# Nav_MCU_IO.net
KiCad netlist of a schematic drawn in Altium Designer
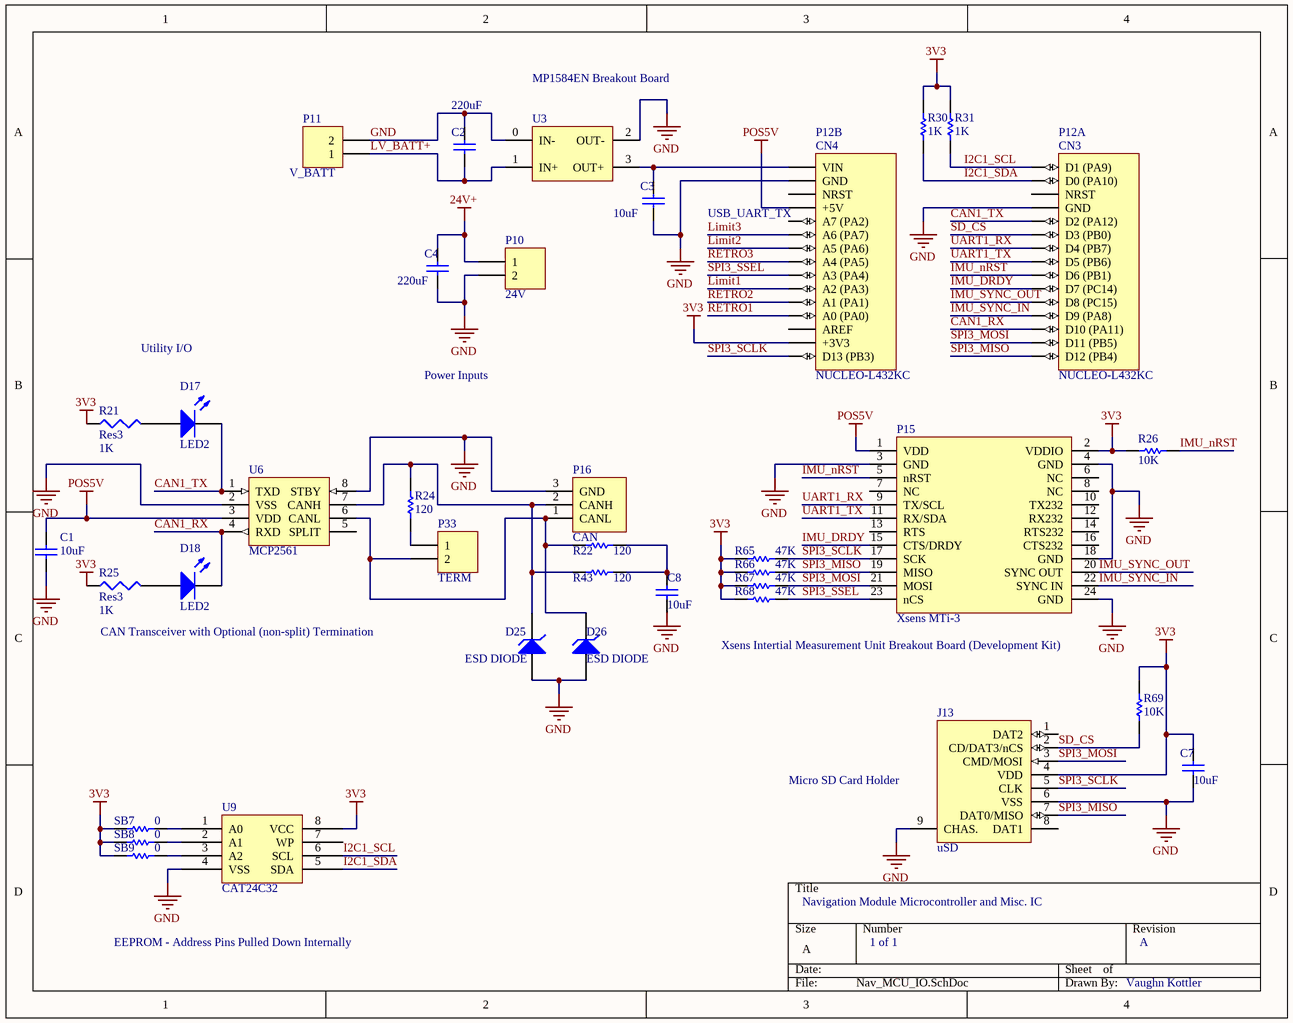
[diagram p0: Nav_MCU_IO.SchDoc]

(export (version "E")
  (design (tool "Eeschema 10.0.6"))
  (components
    (comp (ref "C1")
      (value "10uF")
      (footprint "C1206")
      (description "Capacitor")
      (fields (field (name "Comment") "Cap") (field (name "PUBLISHER") "Altium Limited"))
      (libsource (lib "Miscellaneous Devices") (part "Cap"))
    )
    (comp (ref "C2")
      (value "220uF")
      (footprint "CAPR5-4X5")
      (description "Capacitor")
      (fields (field (name "Comment") "Cap") (field (name "PUBLISHER") "Altium Limited"))
      (libsource (lib "Miscellaneous Devices") (part "Cap"))
    )
    (comp (ref "C3")
      (value "10uF")
      (footprint "C1206")
      (description "Capacitor")
      (fields (field (name "Comment") "Cap") (field (name "PUBLISHER") "Altium Limited"))
      (libsource (lib "Miscellaneous Devices") (part "Cap"))
    )
    (comp (ref "C4")
      (value "220uF")
      (footprint "CAPR5-4X5")
      (description "Capacitor")
      (fields (field (name "Comment") "Cap") (field (name "PUBLISHER") "Altium Limited"))
      (libsource (lib "Miscellaneous Devices") (part "Cap"))
    )
    (comp (ref "C7")
      (value "10uF")
      (footprint "C1206")
      (description "Capacitor")
      (fields (field (name "Comment") "Cap") (field (name "PUBLISHER") "Altium Limited"))
      (libsource (lib "Miscellaneous Devices") (part "Cap"))
    )
    (comp (ref "C8")
      (value "10uF")
      (footprint "C1206")
      (description "Capacitor")
      (fields (field (name "Comment") "Cap") (field (name "PUBLISHER") "Altium Limited"))
      (libsource (lib "Miscellaneous Devices") (part "Cap"))
    )
    (comp (ref "D17")
      (value "LED2")
      (footprint "3.2X1.6X1.1")
      (description "Typical RED, GREEN, YELLOW, AMBER GaAs LED")
      (fields (field (name "PUBLISHER") "Altium Limited"))
      (libsource (lib "Miscellaneous Devices") (part "LED2"))
    )
    (comp (ref "D18")
      (value "LED2")
      (footprint "3.2X1.6X1.1")
      (description "Typical RED, GREEN, YELLOW, AMBER GaAs LED")
      (fields (field (name "PUBLISHER") "Altium Limited"))
      (libsource (lib "Miscellaneous Devices") (part "LED2"))
    )
    (comp (ref "D25")
      (value "ESD DIODE")
      (footprint "6-0805_M")
      (description "Zener Diode")
      (fields (field (name "PUBLISHER") "Altium Limited"))
      (libsource (lib "Miscellaneous Devices") (part "D Zener"))
    )
    (comp (ref "D26")
      (value "ESD DIODE")
      (footprint "6-0805_M")
      (description "Zener Diode")
      (fields (field (name "PUBLISHER") "Altium Limited"))
      (libsource (lib "Miscellaneous Devices") (part "D Zener"))
    )
    (comp (ref "J13")
      (value "uSD")
      (footprint "MICRO_SD_HOLDER")
      (libsource (lib "connector") (part "SD Card"))
    )
    (comp (ref "P10")
      (value "24V")
      (footprint "2POS TERM BLOCK")
      (description "Header, 2-Pin")
      (fields (field (name "PUBLISHER") "Altium Limited"))
      (libsource (lib "") (part "Header 2_1"))
    )
    (comp (ref "P11")
      (value "V_BATT")
      (footprint "2POS TERM BLOCK")
      (description "Header, 2-Pin")
      (fields (field (name "PUBLISHER") "Altium Limited"))
      (libsource (lib "Miscellaneous Connectors") (part "Header 2"))
    )
    (comp (ref "P12")
      (value "NUCLEO-L432KC")
      (footprint "NUCLEO-32")
      (description "STM32L432KC Development Board")
      (libsource (lib "ic") (part "NUCLEO-L432KC"))
    )
    (comp (ref "P15")
      (value "Xsens MTi-3")
      (footprint "Xsens")
      (description "IMU Development Board")
      (libsource (lib "ic") (part "Xsens MTi-3"))
    )
    (comp (ref "P16") (value "CAN") (footprint "3POS TERM BLOCK") (libsource (lib "connector") (part "CAN")))
    (comp (ref "P33")
      (value "TERM")
      (footprint "HDR1X2")
      (description "Header, 2-Pin")
      (fields (field (name "PUBLISHER") "Altium Limited"))
      (libsource (lib "") (part "Header 2_1"))
    )
    (comp (ref "R21")
      (value "Res3")
      (footprint "J1-0603")
      (description "Resistor")
      (fields (field (name "ALTIUM_VALUE") "1K") (field (name "PUBLISHER") "Altium Limited"))
      (libsource (lib "Miscellaneous Devices") (part "Res3"))
    )
    (comp (ref "R22")
      (value "120")
      (footprint "6-0805_M")
      (description "Resistor")
      (fields (field (name "Comment") "Res1") (field (name "PUBLISHER") "Altium Limited"))
      (libsource (lib "Miscellaneous Devices") (part "Res1"))
    )
    (comp (ref "R24")
      (value "120")
      (footprint "6-0805_M")
      (description "Resistor")
      (fields (field (name "Comment") "Res1") (field (name "PUBLISHER") "Altium Limited"))
      (libsource (lib "Miscellaneous Devices") (part "Res1"))
    )
    (comp (ref "R25")
      (value "Res3")
      (footprint "J1-0603")
      (description "Resistor")
      (fields (field (name "ALTIUM_VALUE") "1K") (field (name "PUBLISHER") "Altium Limited"))
      (libsource (lib "Miscellaneous Devices") (part "Res3"))
    )
    (comp (ref "R26")
      (value "10K")
      (footprint "6-0805_M")
      (description "Resistor")
      (fields (field (name "Comment") "Res1") (field (name "PUBLISHER") "Altium Limited"))
      (libsource (lib "Miscellaneous Devices") (part "Res1"))
    )
    (comp (ref "R30")
      (value "1K")
      (footprint "6-0805_M")
      (description "Resistor")
      (fields (field (name "Comment") "Res1") (field (name "PUBLISHER") "Altium Limited"))
      (libsource (lib "Miscellaneous Devices") (part "Res1"))
    )
    (comp (ref "R31")
      (value "1K")
      (footprint "6-0805_M")
      (description "Resistor")
      (fields (field (name "Comment") "Res1") (field (name "PUBLISHER") "Altium Limited"))
      (libsource (lib "Miscellaneous Devices") (part "Res1"))
    )
    (comp (ref "R43")
      (value "120")
      (footprint "6-0805_M")
      (description "Resistor")
      (fields (field (name "Comment") "Res1") (field (name "PUBLISHER") "Altium Limited"))
      (libsource (lib "Miscellaneous Devices") (part "Res1"))
    )
    (comp (ref "R65")
      (value "47K")
      (footprint "6-0805_M")
      (description "Resistor")
      (fields (field (name "Comment") "Res1") (field (name "PUBLISHER") "Altium Limited"))
      (libsource (lib "Miscellaneous Devices") (part "Res1"))
    )
    (comp (ref "R66")
      (value "47K")
      (footprint "6-0805_M")
      (description "Resistor")
      (fields (field (name "Comment") "Res1") (field (name "PUBLISHER") "Altium Limited"))
      (libsource (lib "Miscellaneous Devices") (part "Res1"))
    )
    (comp (ref "R67")
      (value "47K")
      (footprint "6-0805_M")
      (description "Resistor")
      (fields (field (name "Comment") "Res1") (field (name "PUBLISHER") "Altium Limited"))
      (libsource (lib "Miscellaneous Devices") (part "Res1"))
    )
    (comp (ref "R68")
      (value "47K")
      (footprint "6-0805_M")
      (description "Resistor")
      (fields (field (name "Comment") "Res1") (field (name "PUBLISHER") "Altium Limited"))
      (libsource (lib "Miscellaneous Devices") (part "Res1"))
    )
    (comp (ref "R69")
      (value "10K")
      (footprint "6-0805_M")
      (description "Resistor")
      (fields (field (name "Comment") "Res1") (field (name "PUBLISHER") "Altium Limited"))
      (libsource (lib "Miscellaneous Devices") (part "Res1"))
    )
    (comp (ref "SB7")
      (value "0")
      (footprint "6-0805_M")
      (description "Resistor")
      (fields (field (name "Comment") "Res1") (field (name "PUBLISHER") "Altium Limited"))
      (libsource (lib "Miscellaneous Devices") (part "Res1"))
    )
    (comp (ref "SB8")
      (value "0")
      (footprint "6-0805_M")
      (description "Resistor")
      (fields (field (name "Comment") "Res1") (field (name "PUBLISHER") "Altium Limited"))
      (libsource (lib "Miscellaneous Devices") (part "Res1"))
    )
    (comp (ref "SB9")
      (value "0")
      (footprint "6-0805_M")
      (description "Resistor")
      (fields (field (name "Comment") "Res1") (field (name "PUBLISHER") "Altium Limited"))
      (libsource (lib "Miscellaneous Devices") (part "Res1"))
    )
    (comp (ref "U3")
      (value "MP1584EN Breakout Board")
      (footprint "MP1584EN Breakout")
      (description "Buck Converter")
      (libsource (lib "ic") (part "MP1584EN Breakout Board"))
    )
    (comp (ref "U6")
      (value "MCP2561")
      (footprint "SO8_L")
      (description "CAN Transciever")
      (libsource (lib "ic") (part "MCP2561"))
    )
    (comp (ref "U9")
      (value "CAT24C32")
      (footprint "SO8_N")
      (description "I2C EEPROM")
      (libsource (lib "ic") (part "CAT24C32"))
    )
  )
  (nets
    (net (code "1") (name "/CAN1_RX") (class "Default")
      (node (ref "D18") (pin "2") (pinfunction "K_2") (pintype "passive"))
      (node (ref "P12") (pin "13") (pinfunction "D10_(PA11)_13") (pintype "bidirectional"))
      (node (ref "U6") (pin "4") (pinfunction "RXD_4") (pintype "output"))
    )
    (net (code "2") (name "/CAN1_TX") (class "Default")
      (node (ref "D17") (pin "2") (pinfunction "K_2") (pintype "passive"))
      (node (ref "P12") (pin "5") (pinfunction "D2_(PA12)_5") (pintype "bidirectional"))
      (node (ref "U6") (pin "1") (pinfunction "TXD_1") (pintype "input"))
    )
    (net (code "3") (name "/I2C1_SCL") (class "Default")
      (node (ref "P12") (pin "1") (pinfunction "D1_(PA9)_1") (pintype "bidirectional"))
      (node (ref "R31") (pin "1") (pinfunction "1_1") (pintype "passive"))
      (node (ref "U9") (pin "6") (pinfunction "SCL_6") (pintype "passive"))
    )
    (net (code "4") (name "/I2C1_SDA") (class "Default")
      (node (ref "P12") (pin "2") (pinfunction "D0_(PA10)_2") (pintype "bidirectional"))
      (node (ref "R30") (pin "1") (pinfunction "1_1") (pintype "passive"))
      (node (ref "U9") (pin "5") (pinfunction "SDA_5") (pintype "passive"))
    )
    (net (code "5") (name "/IMU_DRDY") (class "Default")
      (node (ref "P12") (pin "10") (pinfunction "D7_(PC14)_10") (pintype "bidirectional"))
      (node (ref "P15") (pin "15") (pinfunction "CTS/DRDY_15") (pintype "passive"))
    )
    (net (code "6") (name "/IMU_SYNC_IN") (class "Default")
      (node (ref "P12") (pin "12") (pinfunction "D9_(PA8)_12") (pintype "bidirectional"))
      (node (ref "P15") (pin "22") (pinfunction "SYNC_IN_22") (pintype "passive"))
    )
    (net (code "7") (name "/IMU_SYNC_OUT") (class "Default")
      (node (ref "P12") (pin "11") (pinfunction "D8_(PC15)_11") (pintype "bidirectional"))
      (node (ref "P15") (pin "20") (pinfunction "SYNC_OUT_20") (pintype "passive"))
    )
    (net (code "8") (name "/IMU_nRST") (class "Default")
      (node (ref "P12") (pin "9") (pinfunction "D6_(PB1)_9") (pintype "bidirectional"))
      (node (ref "P15") (pin "5") (pinfunction "nRST_5") (pintype "passive"))
      (node (ref "R26") (pin "1") (pinfunction "1_1") (pintype "passive"))
    )
    (net (code "9") (name "/LV_BATT+") (class "Default")
      (node (ref "C2") (pin "1") (pinfunction "1_1") (pintype "passive"))
      (node (ref "P11") (pin "1") (pinfunction "1_1") (pintype "passive"))
      (node (ref "U3") (pin "1") (pinfunction "IN+_1") (pintype "power_in"))
    )
    (net (code "10") (name "/Limit1") (class "Default")
      (node (ref "P12") (pin "21") (pinfunction "A2_(PA3)_21") (pintype "bidirectional"))
    )
    (net (code "11") (name "/Limit2") (class "Default")
      (node (ref "P12") (pin "24") (pinfunction "A5_(PA6)_24") (pintype "bidirectional"))
    )
    (net (code "12") (name "/Limit3") (class "Default")
      (node (ref "P12") (pin "25") (pinfunction "A6_(PA7)_25") (pintype "bidirectional"))
    )
    (net (code "13") (name "/RETRO1") (class "Default")
      (node (ref "P12") (pin "19") (pinfunction "A0_(PA0)_19") (pintype "bidirectional"))
    )
    (net (code "14") (name "/RETRO2") (class "Default")
      (node (ref "P12") (pin "20") (pinfunction "A1_(PA1)_20") (pintype "bidirectional"))
    )
    (net (code "15") (name "/RETRO3") (class "Default")
      (node (ref "P12") (pin "23") (pinfunction "A4_(PA5)_23") (pintype "bidirectional"))
    )
    (net (code "16") (name "/SD_CS") (class "Default")
      (node (ref "J13") (pin "2") (pinfunction "CD/DAT3/nCS_2") (pintype "bidirectional"))
      (node (ref "P12") (pin "6") (pinfunction "D3_(PB0)_6") (pintype "bidirectional"))
      (node (ref "R69") (pin "2") (pinfunction "2_2") (pintype "passive"))
    )
    (net (code "17") (name "/SPI3_MISO") (class "Default")
      (node (ref "J13") (pin "7") (pinfunction "DAT0/MISO_7") (pintype "bidirectional"))
      (node (ref "P12") (pin "15") (pinfunction "D12_(PB4)_15") (pintype "bidirectional"))
      (node (ref "P15") (pin "19") (pinfunction "MISO_19") (pintype "passive"))
      (node (ref "R66") (pin "2") (pinfunction "2_2") (pintype "passive"))
    )
    (net (code "18") (name "/SPI3_MOSI") (class "Default")
      (node (ref "J13") (pin "3") (pinfunction "CMD/MOSI_3") (pintype "input"))
      (node (ref "P12") (pin "14") (pinfunction "D11_(PB5)_14") (pintype "bidirectional"))
      (node (ref "P15") (pin "21") (pinfunction "MOSI_21") (pintype "passive"))
      (node (ref "R67") (pin "2") (pinfunction "2_2") (pintype "passive"))
    )
    (net (code "19") (name "/SPI3_SCLK") (class "Default")
      (node (ref "J13") (pin "5") (pinfunction "CLK_5") (pintype "passive"))
      (node (ref "P12") (pin "16") (pinfunction "D13_(PB3)_16") (pintype "bidirectional"))
      (node (ref "P15") (pin "17") (pinfunction "SCK_17") (pintype "passive"))
      (node (ref "R65") (pin "2") (pinfunction "2_2") (pintype "passive"))
    )
    (net (code "20") (name "/SPI3_SSEL") (class "Default")
      (node (ref "P12") (pin "22") (pinfunction "A3_(PA4)_22") (pintype "bidirectional"))
      (node (ref "P15") (pin "23") (pinfunction "nCS_23") (pintype "passive"))
      (node (ref "R68") (pin "2") (pinfunction "2_2") (pintype "passive"))
    )
    (net (code "21") (name "/UART1_RX") (class "Default")
      (node (ref "P12") (pin "7") (pinfunction "D4_(PB7)_7") (pintype "bidirectional"))
      (node (ref "P15") (pin "9") (pinfunction "TX/SCL_9") (pintype "passive"))
    )
    (net (code "22") (name "/UART1_TX") (class "Default")
      (node (ref "P12") (pin "8") (pinfunction "D5_(PB6)_8") (pintype "bidirectional"))
      (node (ref "P15") (pin "11") (pinfunction "RX/SDA_11") (pintype "passive"))
    )
    (net (code "23") (name "3V3") (class "Default")
      (node (ref "C7") (pin "2") (pinfunction "2_2") (pintype "passive"))
      (node (ref "J13") (pin "4") (pinfunction "VDD_4") (pintype "power_in"))
      (node (ref "P12") (pin "17") (pinfunction "+3V3_17") (pintype "power_in"))
      (node (ref "P15") (pin "2") (pinfunction "VDDIO_2") (pintype "power_in"))
      (node (ref "R21") (pin "1") (pinfunction "1_1") (pintype "passive"))
      (node (ref "R25") (pin "1") (pinfunction "1_1") (pintype "passive"))
      (node (ref "R26") (pin "2") (pinfunction "2_2") (pintype "passive"))
      (node (ref "R30") (pin "2") (pinfunction "2_2") (pintype "passive"))
      (node (ref "R31") (pin "2") (pinfunction "2_2") (pintype "passive"))
      (node (ref "R65") (pin "1") (pinfunction "1_1") (pintype "passive"))
      (node (ref "R66") (pin "1") (pinfunction "1_1") (pintype "passive"))
      (node (ref "R67") (pin "1") (pinfunction "1_1") (pintype "passive"))
      (node (ref "R68") (pin "1") (pinfunction "1_1") (pintype "passive"))
      (node (ref "R69") (pin "1") (pinfunction "1_1") (pintype "passive"))
      (node (ref "SB7") (pin "2") (pinfunction "2_2") (pintype "passive"))
      (node (ref "SB8") (pin "2") (pinfunction "2_2") (pintype "passive"))
      (node (ref "SB9") (pin "2") (pinfunction "2_2") (pintype "passive"))
      (node (ref "U9") (pin "8") (pinfunction "VCC_8") (pintype "power_in"))
    )
    (net (code "24") (name "24V+") (class "Default")
      (node (ref "C4") (pin "2") (pinfunction "2_2") (pintype "passive"))
      (node (ref "P10") (pin "1") (pinfunction "1_1") (pintype "passive"))
    )
    (net (code "25") (name "GND") (class "Default")
      (node (ref "C1") (pin "1") (pinfunction "1_1") (pintype "passive"))
      (node (ref "C2") (pin "2") (pinfunction "2_2") (pintype "passive"))
      (node (ref "C3") (pin "1") (pinfunction "1_1") (pintype "passive"))
      (node (ref "C4") (pin "1") (pinfunction "1_1") (pintype "passive"))
      (node (ref "C7") (pin "1") (pinfunction "1_1") (pintype "passive"))
      (node (ref "C8") (pin "1") (pinfunction "1_1") (pintype "passive"))
      (node (ref "D25") (pin "1") (pinfunction "A_1") (pintype "passive"))
      (node (ref "D26") (pin "1") (pinfunction "A_1") (pintype "passive"))
      (node (ref "J13") (pin "6") (pinfunction "VSS_6") (pintype "passive"))
      (node (ref "J13") (pin "9") (pinfunction "CHAS._9") (pintype "passive"))
      (node (ref "P10") (pin "2") (pinfunction "2_2") (pintype "passive"))
      (node (ref "P11") (pin "2") (pinfunction "2_2") (pintype "passive"))
      (node (ref "P12") (pin "29") (pinfunction "GND_29") (pintype "power_in"))
      (node (ref "P12") (pin "4") (pinfunction "GND_4") (pintype "power_in"))
      (node (ref "P15") (pin "18") (pinfunction "GND_18") (pintype "passive"))
      (node (ref "P15") (pin "24") (pinfunction "GND_24") (pintype "power_in"))
      (node (ref "P15") (pin "3") (pinfunction "GND_3") (pintype "power_in"))
      (node (ref "P15") (pin "4") (pinfunction "GND_4") (pintype "power_in"))
      (node (ref "P16") (pin "3") (pinfunction "GND_3") (pintype "passive"))
      (node (ref "U3") (pin "0") (pinfunction "IN-_0") (pintype "power_in"))
      (node (ref "U3") (pin "2") (pinfunction "OUT-_2") (pintype "power_in"))
      (node (ref "U6") (pin "2") (pinfunction "VSS_2") (pintype "power_in"))
      (node (ref "U6") (pin "8") (pinfunction "STBY_8") (pintype "input"))
      (node (ref "U9") (pin "4") (pinfunction "VSS_4") (pintype "passive"))
    )
    (net (code "26") (name "Net-(C8-Pad2)") (class "Default")
      (node (ref "C8") (pin "2") (pinfunction "2_2") (pintype "passive"))
      (node (ref "R22") (pin "1") (pinfunction "1_1") (pintype "passive"))
      (node (ref "R43") (pin "1") (pinfunction "1_1") (pintype "passive"))
    )
    (net (code "27") (name "Net-(D17-A)") (class "Default")
      (node (ref "D17") (pin "1") (pinfunction "A_1") (pintype "passive"))
      (node (ref "R21") (pin "2") (pinfunction "2_2") (pintype "passive"))
    )
    (net (code "28") (name "Net-(D18-A)") (class "Default")
      (node (ref "D18") (pin "1") (pinfunction "A_1") (pintype "passive"))
      (node (ref "R25") (pin "2") (pinfunction "2_2") (pintype "passive"))
    )
    (net (code "29") (name "Net-(D25-K)") (class "Default")
      (node (ref "D25") (pin "2") (pinfunction "K_2") (pintype "passive"))
      (node (ref "P16") (pin "2") (pinfunction "CANH_2") (pintype "passive"))
      (node (ref "R24") (pin "2") (pinfunction "2_2") (pintype "passive"))
      (node (ref "R43") (pin "2") (pinfunction "2_2") (pintype "passive"))
      (node (ref "U6") (pin "7") (pinfunction "CANH_7") (pintype "passive"))
    )
    (net (code "30") (name "Net-(D26-K)") (class "Default")
      (node (ref "D26") (pin "2") (pinfunction "K_2") (pintype "passive"))
      (node (ref "P16") (pin "1") (pinfunction "CANL_1") (pintype "passive"))
      (node (ref "P33") (pin "2") (pinfunction "2_2") (pintype "passive"))
      (node (ref "R22") (pin "2") (pinfunction "2_2") (pintype "passive"))
      (node (ref "U6") (pin "6") (pinfunction "CANL_6") (pintype "passive"))
    )
    (net (code "31") (name "Net-(P12B-VIN)") (class "Default")
      (node (ref "C3") (pin "2") (pinfunction "2_2") (pintype "passive"))
      (node (ref "P12") (pin "30") (pinfunction "VIN_30") (pintype "power_in"))
      (node (ref "U3") (pin "3") (pinfunction "OUT+_3") (pintype "power_in"))
    )
    (net (code "32") (name "Net-(P33-Pad1)") (class "Default")
      (node (ref "P33") (pin "1") (pinfunction "1_1") (pintype "passive"))
      (node (ref "R24") (pin "1") (pinfunction "1_1") (pintype "passive"))
    )
    (net (code "33") (name "Net-(U9-A0)") (class "Default")
      (node (ref "SB7") (pin "1") (pinfunction "1_1") (pintype "passive"))
      (node (ref "U9") (pin "1") (pinfunction "A0_1") (pintype "passive"))
    )
    (net (code "34") (name "Net-(U9-A1)") (class "Default")
      (node (ref "SB8") (pin "1") (pinfunction "1_1") (pintype "passive"))
      (node (ref "U9") (pin "2") (pinfunction "A1_2") (pintype "passive"))
    )
    (net (code "35") (name "Net-(U9-A2)") (class "Default")
      (node (ref "SB9") (pin "1") (pinfunction "1_1") (pintype "passive"))
      (node (ref "U9") (pin "3") (pinfunction "A2_3") (pintype "passive"))
    )
    (net (code "36") (name "POS5V") (class "Default")
      (node (ref "C1") (pin "2") (pinfunction "2_2") (pintype "passive"))
      (node (ref "P12") (pin "27") (pinfunction "+5V_27") (pintype "power_in"))
      (node (ref "P15") (pin "1") (pinfunction "VDD_1") (pintype "power_in"))
      (node (ref "U6") (pin "3") (pinfunction "VDD_3") (pintype "passive"))
    )
    (net (code "37") (name "unconnected-(J13-DAT1-Pad8)") (class "Default")
      (node (ref "J13") (pin "8") (pinfunction "DAT1_8") (pintype "passive"))
    )
    (net (code "38") (name "unconnected-(J13-DAT2-Pad1)") (class "Default")
      (node (ref "J13") (pin "1") (pinfunction "DAT2_1") (pintype "bidirectional"))
    )
    (net (code "39") (name "unconnected-(P12A-NRST-Pad3)") (class "Default")
      (node (ref "P12") (pin "3") (pinfunction "NRST_3") (pintype "passive"))
    )
    (net (code "40") (name "unconnected-(P12B-A7_(PA2)-Pad26)") (class "Default")
      (node (ref "P12") (pin "26") (pinfunction "A7_(PA2)_26") (pintype "bidirectional"))
    )
    (net (code "41") (name "unconnected-(P12B-AREF-Pad18)") (class "Default")
      (node (ref "P12") (pin "18") (pinfunction "AREF_18") (pintype "passive"))
    )
    (net (code "42") (name "unconnected-(P12B-NRST-Pad28)") (class "Default")
      (node (ref "P12") (pin "28") (pinfunction "NRST_28") (pintype "passive"))
    )
    (net (code "43") (name "unconnected-(P15-CTS232-Pad16)") (class "Default")
      (node (ref "P15") (pin "16") (pinfunction "CTS232_16") (pintype "passive"))
    )
    (net (code "44") (name "unconnected-(P15-NC-Pad6)") (class "Default")
      (node (ref "P15") (pin "6") (pinfunction "NC_6") (pintype "passive"))
    )
    (net (code "45") (name "unconnected-(P15-NC-Pad7)") (class "Default")
      (node (ref "P15") (pin "7") (pinfunction "NC_7") (pintype "passive"))
    )
    (net (code "46") (name "unconnected-(P15-NC-Pad8)") (class "Default")
      (node (ref "P15") (pin "8") (pinfunction "NC_8") (pintype "passive"))
    )
    (net (code "47") (name "unconnected-(P15-RTS-Pad13)") (class "Default")
      (node (ref "P15") (pin "13") (pinfunction "RTS_13") (pintype "passive"))
    )
    (net (code "48") (name "unconnected-(P15-RTS232-Pad14)") (class "Default")
      (node (ref "P15") (pin "14") (pinfunction "RTS232_14") (pintype "passive"))
    )
    (net (code "49") (name "unconnected-(P15-RX232-Pad12)") (class "Default")
      (node (ref "P15") (pin "12") (pinfunction "RX232_12") (pintype "passive"))
    )
    (net (code "50") (name "unconnected-(P15-TX232-Pad10)") (class "Default")
      (node (ref "P15") (pin "10") (pinfunction "TX232_10") (pintype "passive"))
    )
    (net (code "51") (name "unconnected-(U6-SPLIT-Pad5)") (class "Default")
      (node (ref "U6") (pin "5") (pinfunction "SPLIT_5") (pintype "passive"))
    )
    (net (code "52") (name "unconnected-(U9-WP-Pad7)") (class "Default")
      (node (ref "U9") (pin "7") (pinfunction "WP_7") (pintype "passive"))
    )
  )
)
